# KarateLight.net
KiCad netlist of a schematic drawn in EAGLE
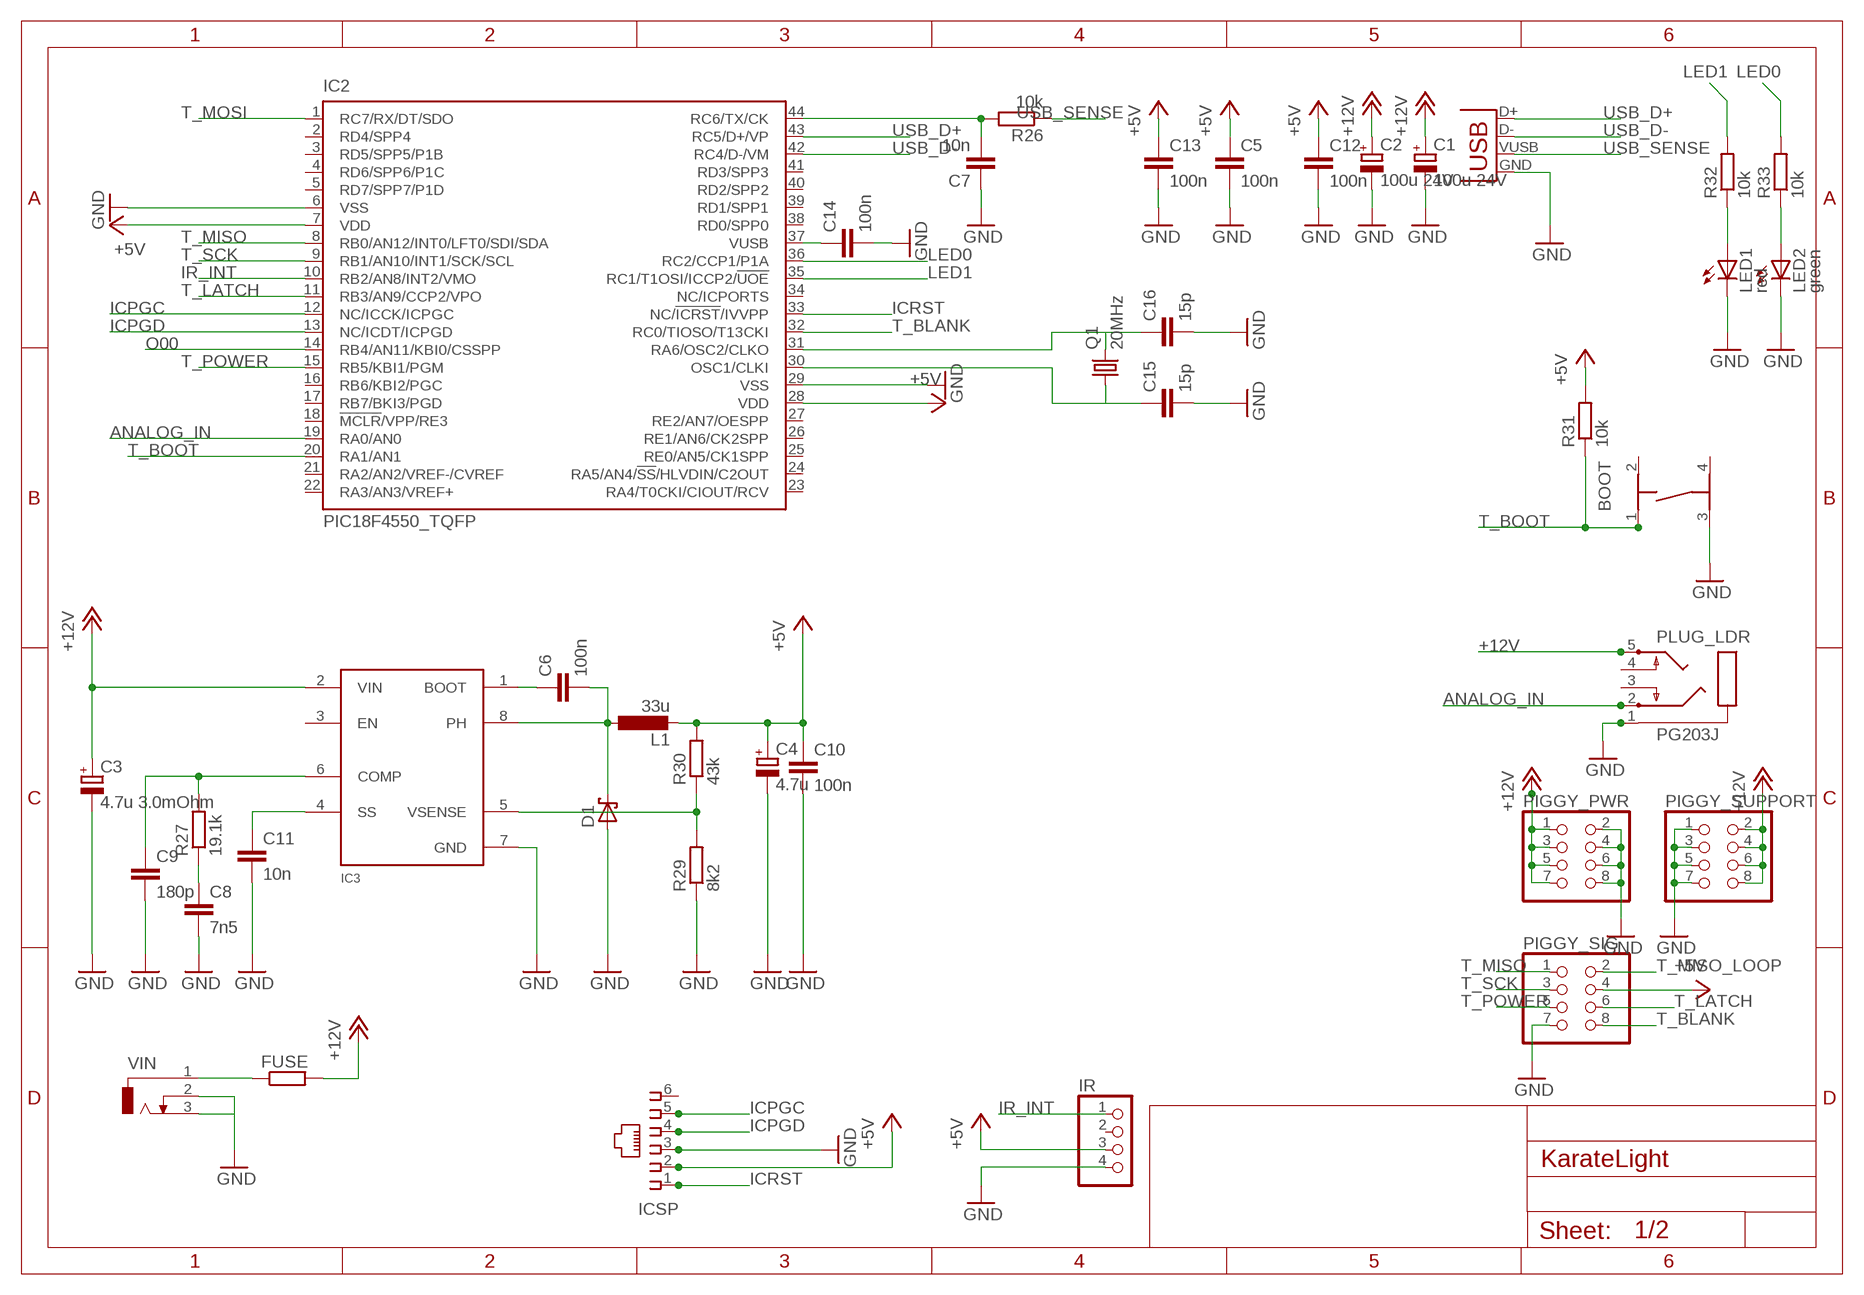
[diagram p0: schematic, sheet 1]
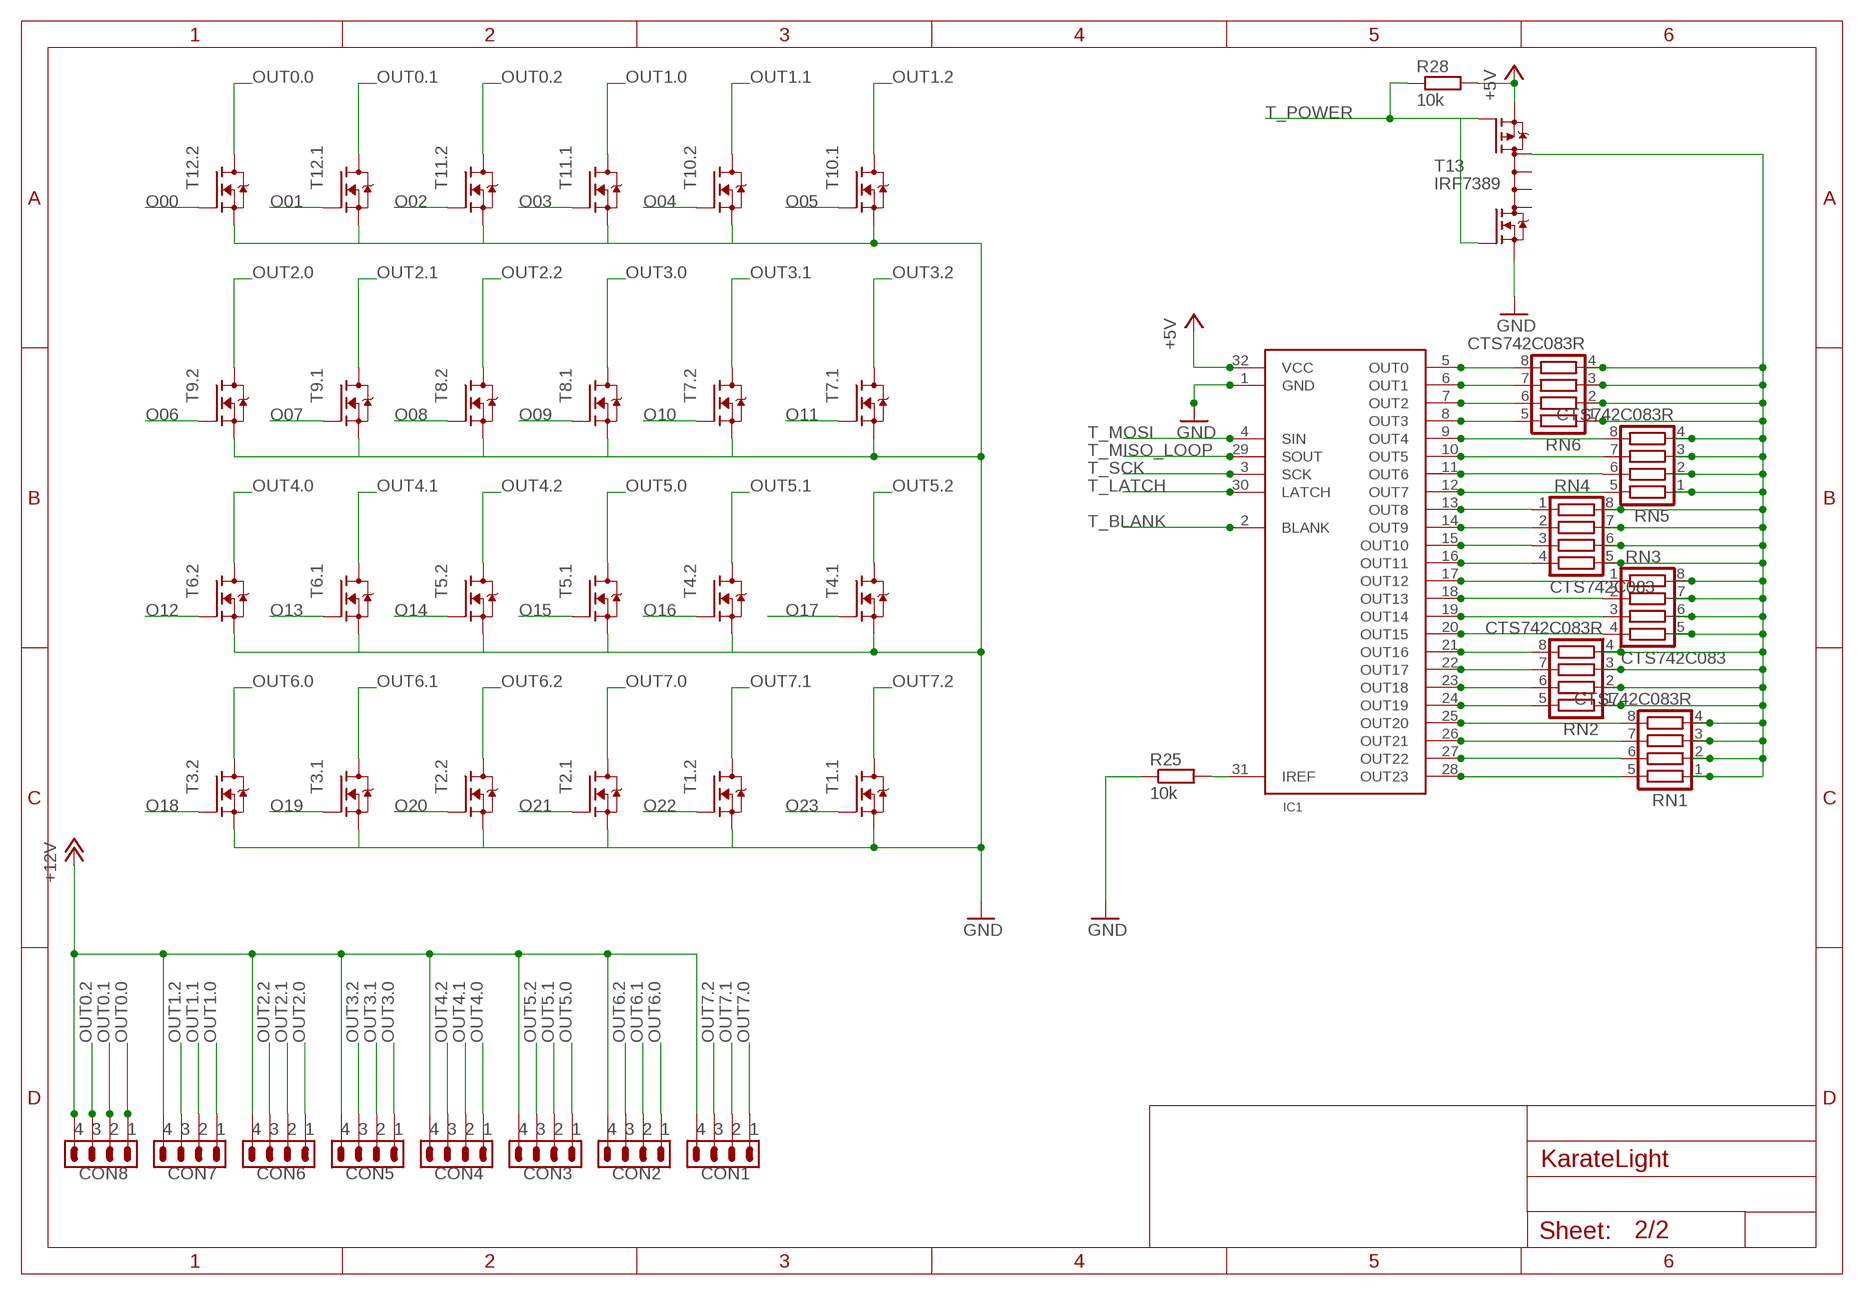
[diagram p1: schematic, sheet 2]

(export (version "E")
  (design (tool "Eeschema 10.0.6"))
  (components
    (comp (ref "CON1")
      (value "PINHEAD_4W")
      (footprint "eagle-import:MA04-1")
      (libsource (lib "eagle-import") (part "PINHEAD_4W"))
    )
    (comp (ref "CON2")
      (value "PINHEAD_4W")
      (footprint "eagle-import:MA04-1")
      (libsource (lib "eagle-import") (part "PINHEAD_4W"))
    )
    (comp (ref "CON3")
      (value "PINHEAD_4W")
      (footprint "eagle-import:MA04-1")
      (libsource (lib "eagle-import") (part "PINHEAD_4W"))
    )
    (comp (ref "CON4")
      (value "PINHEAD_4W")
      (footprint "eagle-import:MA04-1")
      (libsource (lib "eagle-import") (part "PINHEAD_4W"))
    )
    (comp (ref "CON5")
      (value "PINHEAD_4W")
      (footprint "eagle-import:MA04-1")
      (libsource (lib "eagle-import") (part "PINHEAD_4W"))
    )
    (comp (ref "CON6")
      (value "PINHEAD_4W")
      (footprint "eagle-import:MA04-1")
      (libsource (lib "eagle-import") (part "PINHEAD_4W"))
    )
    (comp (ref "CON7")
      (value "PINHEAD_4W")
      (footprint "eagle-import:MA04-1")
      (libsource (lib "eagle-import") (part "PINHEAD_4W"))
    )
    (comp (ref "CON8")
      (value "PINHEAD_4W")
      (footprint "eagle-import:MA04-1")
      (libsource (lib "eagle-import") (part "PINHEAD_4W"))
    )
    (comp (ref "IC1")
      (value "TLC5947")
      (footprint "eagle-import:TSSOP32")
      (libsource (lib "eagle-import") (part "TLC5947"))
    )
    (comp (ref "R25")
      (value "10k")
      (footprint "eagle-import:R0603")
      (libsource (lib "eagle-import") (part "R-EU_R0603"))
    )
    (comp (ref "R28")
      (value "10k")
      (footprint "eagle-import:R0603")
      (libsource (lib "eagle-import") (part "R-EU_R0603"))
    )
    (comp (ref "RN1")
      (value "CTS742C083R")
      (footprint "eagle-import:CTS742C083")
      (libsource (lib "eagle-import") (part "CTS742C083R"))
    )
    (comp (ref "RN2")
      (value "CTS742C083R")
      (footprint "eagle-import:CTS742C083")
      (libsource (lib "eagle-import") (part "CTS742C083R"))
    )
    (comp (ref "RN3")
      (value "CTS742C083")
      (footprint "eagle-import:CTS742C083")
      (fields (field (name "OC_FARNELL") "unknown") (field (name "OC_NEWARK") "unknown"))
      (libsource (lib "eagle-import") (part "CTS742C083"))
    )
    (comp (ref "RN4")
      (value "CTS742C083")
      (footprint "eagle-import:CTS742C083")
      (libsource (lib "eagle-import") (part "CTS742C083"))
    )
    (comp (ref "RN5")
      (value "CTS742C083R")
      (footprint "eagle-import:CTS742C083")
      (libsource (lib "eagle-import") (part "CTS742C083R"))
    )
    (comp (ref "RN6")
      (value "CTS742C083R")
      (footprint "eagle-import:CTS742C083")
      (libsource (lib "eagle-import") (part "CTS742C083R"))
    )
    (comp (ref "T1")
      (value "IRF7103")
      (footprint "eagle-import:SO08-IRF")
      (libsource (lib "eagle-import") (part "IRF7103"))
    )
    (comp (ref "T2")
      (value "IRF7103")
      (footprint "eagle-import:SO08-IRF")
      (libsource (lib "eagle-import") (part "IRF7103"))
    )
    (comp (ref "T3")
      (value "IRF7103")
      (footprint "eagle-import:SO08-IRF")
      (libsource (lib "eagle-import") (part "IRF7103"))
    )
    (comp (ref "T4")
      (value "IRF7103")
      (footprint "eagle-import:SO08-IRF")
      (libsource (lib "eagle-import") (part "IRF7103"))
    )
    (comp (ref "T5")
      (value "IRF7103")
      (footprint "eagle-import:SO08-IRF")
      (libsource (lib "eagle-import") (part "IRF7103"))
    )
    (comp (ref "T6")
      (value "IRF7103")
      (footprint "eagle-import:SO08-IRF")
      (libsource (lib "eagle-import") (part "IRF7103"))
    )
    (comp (ref "T7")
      (value "IRF7103")
      (footprint "eagle-import:SO08-IRF")
      (libsource (lib "eagle-import") (part "IRF7103"))
    )
    (comp (ref "T8")
      (value "IRF7103")
      (footprint "eagle-import:SO08-IRF")
      (libsource (lib "eagle-import") (part "IRF7103"))
    )
    (comp (ref "T9")
      (value "IRF7103")
      (footprint "eagle-import:SO08-IRF")
      (libsource (lib "eagle-import") (part "IRF7103"))
    )
    (comp (ref "T10")
      (value "IRF7103")
      (footprint "eagle-import:SO08-IRF")
      (libsource (lib "eagle-import") (part "IRF7103"))
    )
    (comp (ref "T11")
      (value "IRF7103")
      (footprint "eagle-import:SO08-IRF")
      (libsource (lib "eagle-import") (part "IRF7103"))
    )
    (comp (ref "T12")
      (value "IRF7103")
      (footprint "eagle-import:SO08-IRF")
      (libsource (lib "eagle-import") (part "IRF7103"))
    )
    (comp (ref "T13")
      (value "IRF7389")
      (footprint "eagle-import:SO08-IRF")
      (libsource (lib "eagle-import") (part "IRF7389"))
    )
    (comp (ref "BOOT")
      (value "TASTER-9314_SMD")
      (footprint "eagle-import:TASTER-9314_SMD")
      (libsource (lib "eagle-import") (part "TASTER-9314_SMD"))
    )
    (comp (ref "C1")
      (value "100u 24V")
      (footprint "eagle-import:153CLV-0605")
      (libsource (lib "eagle-import") (part "CPOL-EU153CLV-0605"))
    )
    (comp (ref "C2")
      (value "100u 24V")
      (footprint "eagle-import:153CLV-0605")
      (libsource (lib "eagle-import") (part "CPOL-EU153CLV-0605"))
    )
    (comp (ref "C3")
      (value "4.7u 3.0mOhm")
      (footprint "eagle-import:153CLV-0405")
      (libsource (lib "eagle-import") (part "CPOL-EU153CLV-0405"))
    )
    (comp (ref "C4")
      (value "4.7u")
      (footprint "eagle-import:153CLV-0405")
      (libsource (lib "eagle-import") (part "CPOL-EU153CLV-0405"))
    )
    (comp (ref "C5")
      (value "100n")
      (footprint "eagle-import:C0805K")
      (libsource (lib "eagle-import") (part "C-EUC0805K"))
    )
    (comp (ref "C6")
      (value "100n")
      (footprint "eagle-import:C0603")
      (libsource (lib "eagle-import") (part "C-EUC0603"))
    )
    (comp (ref "C7")
      (value "10n")
      (footprint "eagle-import:C0603")
      (libsource (lib "eagle-import") (part "C-EUC0603"))
    )
    (comp (ref "C8")
      (value "7n5")
      (footprint "eagle-import:C0603")
      (libsource (lib "eagle-import") (part "C-EUC0603"))
    )
    (comp (ref "C9")
      (value "180p")
      (footprint "eagle-import:C0603")
      (libsource (lib "eagle-import") (part "C-EUC0603"))
    )
    (comp (ref "C10")
      (value "100n")
      (footprint "eagle-import:C0603")
      (libsource (lib "eagle-import") (part "C-EUC0603"))
    )
    (comp (ref "C11")
      (value "10n")
      (footprint "eagle-import:C0603")
      (libsource (lib "eagle-import") (part "C-EUC0603"))
    )
    (comp (ref "C12")
      (value "100n")
      (footprint "eagle-import:C0603")
      (libsource (lib "eagle-import") (part "C-EUC0603"))
    )
    (comp (ref "C13")
      (value "100n")
      (footprint "eagle-import:C0805K")
      (libsource (lib "eagle-import") (part "C-EUC0805K"))
    )
    (comp (ref "C14")
      (value "100n")
      (footprint "eagle-import:C0805K")
      (libsource (lib "eagle-import") (part "C-EUC0805K"))
    )
    (comp (ref "C15")
      (value "15p")
      (footprint "eagle-import:C0603")
      (libsource (lib "eagle-import") (part "C-EUC0603"))
    )
    (comp (ref "C16")
      (value "15p")
      (footprint "eagle-import:C0603")
      (libsource (lib "eagle-import") (part "C-EUC0603"))
    )
    (comp (ref "D1")
      (value "SCHOTTKY-DIODESMD")
      (footprint "eagle-import:SMB")
      (libsource (lib "eagle-import") (part "SCHOTTKY-DIODESMD"))
    )
    (comp (ref "FUSE")
      (value "R-EU_R4527")
      (footprint "eagle-import:R4527")
      (libsource (lib "eagle-import") (part "R-EU_R4527"))
    )
    (comp (ref "IC2")
      (value "PIC18F4550_TQFP")
      (footprint "eagle-import:TQFP44")
      (libsource (lib "eagle-import") (part "PIC18F4_TQFP550"))
    )
    (comp (ref "IC3")
      (value "TPS54232")
      (footprint "eagle-import:SO-08")
      (libsource (lib "eagle-import") (part "TPS54232"))
    )
    (comp (ref "ICSP")
      (value "520250-3")
      (footprint "eagle-import:520250-3")
      (libsource (lib "eagle-import") (part "520250-3"))
    )
    (comp (ref "IR")
      (value "PINHD-1X4")
      (footprint "eagle-import:1X04")
      (libsource (lib "eagle-import") (part "PINHD-1X4"))
    )
    (comp (ref "L1")
      (value "33u")
      (footprint "eagle-import:PIS2816")
      (libsource (lib "eagle-import") (part "L-EUPIS2816"))
    )
    (comp (ref "LED1")
      (value "red")
      (footprint "eagle-import:CHIP-LED0805")
      (libsource (lib "eagle-import") (part "LEDCHIP-LED0805"))
    )
    (comp (ref "LED2")
      (value "green")
      (footprint "eagle-import:CHIP-LED0805")
      (libsource (lib "eagle-import") (part "LEDCHIP-LED0805"))
    )
    (comp (ref "PIGGY_PWR")
      (value "PINHD-2X4")
      (footprint "eagle-import:2X04")
      (libsource (lib "eagle-import") (part "PINHD-2X4"))
    )
    (comp (ref "PIGGY_SIG")
      (value "PINHD-2X4")
      (footprint "eagle-import:2X04")
      (libsource (lib "eagle-import") (part "PINHD-2X4"))
    )
    (comp (ref "PIGGY_SUPPORT")
      (value "PINHD-2X4")
      (footprint "eagle-import:2X04")
      (libsource (lib "eagle-import") (part "PINHD-2X4"))
    )
    (comp (ref "PLUG_LDR")
      (value "PG203J")
      (footprint "eagle-import:PG203J")
      (libsource (lib "eagle-import") (part "PG203J"))
    )
    (comp (ref "PLUG_USB")
      (value "USB-B-S")
      (footprint "eagle-import:USB-B-SMT")
      (libsource (lib "eagle-import") (part "USB-B-S"))
    )
    (comp (ref "Q1")
      (value "20MHz")
      (footprint "eagle-import:HC49UP")
      (libsource (lib "eagle-import") (part "CRYSTALHC49UP"))
    )
    (comp (ref "R26")
      (value "10k")
      (footprint "eagle-import:R0603")
      (libsource (lib "eagle-import") (part "R-EU_R0603"))
    )
    (comp (ref "R27")
      (value "19.1k")
      (footprint "eagle-import:R0603")
      (libsource (lib "eagle-import") (part "R-EU_R0603"))
    )
    (comp (ref "R29")
      (value "8k2")
      (footprint "eagle-import:R0603")
      (libsource (lib "eagle-import") (part "R-EU_R0603"))
    )
    (comp (ref "R30")
      (value "43k")
      (footprint "eagle-import:R0603")
      (libsource (lib "eagle-import") (part "R-EU_R0603"))
    )
    (comp (ref "R31")
      (value "10k")
      (footprint "eagle-import:R0603")
      (libsource (lib "eagle-import") (part "R-EU_R0603"))
    )
    (comp (ref "R32")
      (value "10k")
      (footprint "eagle-import:R0603")
      (libsource (lib "eagle-import") (part "R-EU_R0603"))
    )
    (comp (ref "R33")
      (value "10k")
      (footprint "eagle-import:R0603")
      (libsource (lib "eagle-import") (part "R-EU_R0603"))
    )
    (comp (ref "VIN")
      (value "DCJ0303")
      (footprint "eagle-import:DCJ0303")
      (libsource (lib "eagle-import") (part "DCJ0303"))
    )
  )
  (nets
    (net (code "1") (name "+5V") (class "Default")
      (node (ref "C10") (pin "1") (pinfunction "1_1") (pintype "passive"))
      (node (ref "C12") (pin "1") (pinfunction "1_1") (pintype "passive"))
      (node (ref "C13") (pin "1") (pinfunction "1_1") (pintype "passive"))
      (node (ref "C4") (pin "+") (pinfunction "+_+") (pintype "passive"))
      (node (ref "C5") (pin "1") (pinfunction "1_1") (pintype "passive"))
      (node (ref "IC1") (pin "32") (pinfunction "VCC_32") (pintype "bidirectional"))
      (node (ref "IC2") (pin "28") (pinfunction "VDD_28") (pintype "power_in"))
      (node (ref "IC2") (pin "7") (pinfunction "VDD_7") (pintype "power_in"))
      (node (ref "ICSP") (pin "2") (pinfunction "2_2") (pintype "passive"))
      (node (ref "IR") (pin "3") (pinfunction "3_3") (pintype "passive"))
      (node (ref "L1") (pin "2") (pinfunction "2_2") (pintype "passive"))
      (node (ref "PIGGY_SIG") (pin "4") (pinfunction "4_4") (pintype "passive"))
      (node (ref "R28") (pin "2") (pinfunction "2_2") (pintype "passive"))
      (node (ref "R30") (pin "2") (pinfunction "2_2") (pintype "passive"))
      (node (ref "R31") (pin "2") (pinfunction "2_2") (pintype "passive"))
      (node (ref "T13") (pin "3") (pinfunction "P-S_3") (pintype "passive"))
    )
    (net (code "2") (name "+12V") (class "Default")
      (node (ref "C1") (pin "+") (pinfunction "+_+") (pintype "passive"))
      (node (ref "C2") (pin "+") (pinfunction "+_+") (pintype "passive"))
      (node (ref "C3") (pin "+") (pinfunction "+_+") (pintype "passive"))
      (node (ref "CON1") (pin "4") (pinfunction "4_4") (pintype "bidirectional"))
      (node (ref "CON2") (pin "4") (pinfunction "4_4") (pintype "bidirectional"))
      (node (ref "CON3") (pin "4") (pinfunction "4_4") (pintype "bidirectional"))
      (node (ref "CON4") (pin "4") (pinfunction "4_4") (pintype "bidirectional"))
      (node (ref "CON5") (pin "4") (pinfunction "4_4") (pintype "bidirectional"))
      (node (ref "CON6") (pin "4") (pinfunction "4_4") (pintype "bidirectional"))
      (node (ref "CON7") (pin "4") (pinfunction "4_4") (pintype "bidirectional"))
      (node (ref "CON8") (pin "4") (pinfunction "4_4") (pintype "bidirectional"))
      (node (ref "FUSE") (pin "2") (pinfunction "2_2") (pintype "passive"))
      (node (ref "IC3") (pin "2") (pinfunction "VIN_2") (pintype "bidirectional"))
      (node (ref "PIGGY_PWR") (pin "1") (pinfunction "1_1") (pintype "passive"))
      (node (ref "PIGGY_PWR") (pin "3") (pinfunction "3_3") (pintype "passive"))
      (node (ref "PIGGY_PWR") (pin "5") (pinfunction "5_5") (pintype "passive"))
      (node (ref "PIGGY_PWR") (pin "7") (pinfunction "7_7") (pintype "passive"))
      (node (ref "PIGGY_SUPPORT") (pin "2") (pinfunction "2_2") (pintype "passive"))
      (node (ref "PIGGY_SUPPORT") (pin "4") (pinfunction "4_4") (pintype "passive"))
      (node (ref "PIGGY_SUPPORT") (pin "6") (pinfunction "6_6") (pintype "passive"))
      (node (ref "PIGGY_SUPPORT") (pin "8") (pinfunction "8_8") (pintype "passive"))
      (node (ref "PLUG_LDR") (pin "5") (pinfunction "5_5") (pintype "passive"))
    )
    (net (code "3") (name "ANALOG_IN") (class "Default")
      (node (ref "IC2") (pin "19") (pinfunction "RA0/AN0_19") (pintype "bidirectional"))
      (node (ref "PLUG_LDR") (pin "2") (pinfunction "2_2") (pintype "passive"))
    )
    (net (code "4") (name "GND") (class "Default")
      (node (ref "BOOT") (pin "3") (pinfunction "3_3") (pintype "passive"))
      (node (ref "C1") (pin "-") (pinfunction "-_-") (pintype "passive"))
      (node (ref "C10") (pin "2") (pinfunction "2_2") (pintype "passive"))
      (node (ref "C11") (pin "2") (pinfunction "2_2") (pintype "passive"))
      (node (ref "C12") (pin "2") (pinfunction "2_2") (pintype "passive"))
      (node (ref "C13") (pin "2") (pinfunction "2_2") (pintype "passive"))
      (node (ref "C14") (pin "2") (pinfunction "2_2") (pintype "passive"))
      (node (ref "C15") (pin "2") (pinfunction "2_2") (pintype "passive"))
      (node (ref "C16") (pin "2") (pinfunction "2_2") (pintype "passive"))
      (node (ref "C2") (pin "-") (pinfunction "-_-") (pintype "passive"))
      (node (ref "C3") (pin "-") (pinfunction "-_-") (pintype "passive"))
      (node (ref "C4") (pin "-") (pinfunction "-_-") (pintype "passive"))
      (node (ref "C5") (pin "2") (pinfunction "2_2") (pintype "passive"))
      (node (ref "C7") (pin "1") (pinfunction "1_1") (pintype "passive"))
      (node (ref "C8") (pin "2") (pinfunction "2_2") (pintype "passive"))
      (node (ref "C9") (pin "2") (pinfunction "2_2") (pintype "passive"))
      (node (ref "D1") (pin "A") (pinfunction "A_A") (pintype "passive"))
      (node (ref "IC1") (pin "1") (pinfunction "GND_1") (pintype "bidirectional"))
      (node (ref "IC2") (pin "29") (pinfunction "VSS_29") (pintype "power_in"))
      (node (ref "IC2") (pin "6") (pinfunction "VSS_6") (pintype "power_in"))
      (node (ref "IC3") (pin "7") (pinfunction "GND_7") (pintype "bidirectional"))
      (node (ref "ICSP") (pin "3") (pinfunction "3_3") (pintype "passive"))
      (node (ref "IR") (pin "4") (pinfunction "4_4") (pintype "passive"))
      (node (ref "LED1") (pin "C") (pinfunction "C_C") (pintype "passive"))
      (node (ref "LED2") (pin "C") (pinfunction "C_C") (pintype "passive"))
      (node (ref "PIGGY_PWR") (pin "2") (pinfunction "2_2") (pintype "passive"))
      (node (ref "PIGGY_PWR") (pin "4") (pinfunction "4_4") (pintype "passive"))
      (node (ref "PIGGY_PWR") (pin "6") (pinfunction "6_6") (pintype "passive"))
      (node (ref "PIGGY_PWR") (pin "8") (pinfunction "8_8") (pintype "passive"))
      (node (ref "PIGGY_SIG") (pin "7") (pinfunction "7_7") (pintype "passive"))
      (node (ref "PIGGY_SUPPORT") (pin "1") (pinfunction "1_1") (pintype "passive"))
      (node (ref "PIGGY_SUPPORT") (pin "3") (pinfunction "3_3") (pintype "passive"))
      (node (ref "PIGGY_SUPPORT") (pin "5") (pinfunction "5_5") (pintype "passive"))
      (node (ref "PIGGY_SUPPORT") (pin "7") (pinfunction "7_7") (pintype "passive"))
      (node (ref "PLUG_LDR") (pin "1") (pinfunction "1_1") (pintype "passive"))
      (node (ref "PLUG_USB") (pin "GND") (pinfunction "GND_GND") (pintype "bidirectional"))
      (node (ref "R25") (pin "1") (pinfunction "1_1") (pintype "passive"))
      (node (ref "R29") (pin "1") (pinfunction "1_1") (pintype "passive"))
      (node (ref "T1") (pin "1") (pinfunction "S_1") (pintype "passive"))
      (node (ref "T1") (pin "3") (pinfunction "S_3") (pintype "passive"))
      (node (ref "T10") (pin "1") (pinfunction "S_1") (pintype "passive"))
      (node (ref "T10") (pin "3") (pinfunction "S_3") (pintype "passive"))
      (node (ref "T11") (pin "1") (pinfunction "S_1") (pintype "passive"))
      (node (ref "T11") (pin "3") (pinfunction "S_3") (pintype "passive"))
      (node (ref "T12") (pin "1") (pinfunction "S_1") (pintype "passive"))
      (node (ref "T12") (pin "3") (pinfunction "S_3") (pintype "passive"))
      (node (ref "T13") (pin "1") (pinfunction "N-S_1") (pintype "passive"))
      (node (ref "T2") (pin "1") (pinfunction "S_1") (pintype "passive"))
      (node (ref "T2") (pin "3") (pinfunction "S_3") (pintype "passive"))
      (node (ref "T3") (pin "1") (pinfunction "S_1") (pintype "passive"))
      (node (ref "T3") (pin "3") (pinfunction "S_3") (pintype "passive"))
      (node (ref "T4") (pin "1") (pinfunction "S_1") (pintype "passive"))
      (node (ref "T4") (pin "3") (pinfunction "S_3") (pintype "passive"))
      (node (ref "T5") (pin "1") (pinfunction "S_1") (pintype "passive"))
      (node (ref "T5") (pin "3") (pinfunction "S_3") (pintype "passive"))
      (node (ref "T6") (pin "1") (pinfunction "S_1") (pintype "passive"))
      (node (ref "T6") (pin "3") (pinfunction "S_3") (pintype "passive"))
      (node (ref "T7") (pin "1") (pinfunction "S_1") (pintype "passive"))
      (node (ref "T7") (pin "3") (pinfunction "S_3") (pintype "passive"))
      (node (ref "T8") (pin "1") (pinfunction "S_1") (pintype "passive"))
      (node (ref "T8") (pin "3") (pinfunction "S_3") (pintype "passive"))
      (node (ref "T9") (pin "1") (pinfunction "S_1") (pintype "passive"))
      (node (ref "T9") (pin "3") (pinfunction "S_3") (pintype "passive"))
      (node (ref "VIN") (pin "2") (pinfunction "2_2") (pintype "passive"))
      (node (ref "VIN") (pin "3") (pinfunction "3_3") (pintype "passive"))
    )
    (net (code "5") (name "ICPGC") (class "Default")
      (node (ref "IC2") (pin "12") (pinfunction "NC/ICCK/ICPGC_12") (pintype "bidirectional"))
      (node (ref "ICSP") (pin "5") (pinfunction "5_5") (pintype "passive"))
    )
    (net (code "6") (name "ICPGD") (class "Default")
      (node (ref "IC2") (pin "13") (pinfunction "NC/ICDT/ICPGD_13") (pintype "bidirectional"))
      (node (ref "ICSP") (pin "4") (pinfunction "4_4") (pintype "passive"))
    )
    (net (code "7") (name "ICRST") (class "Default")
      (node (ref "IC2") (pin "33") (pinfunction "NC/~{ICRST}/IVVPP_33") (pintype "input"))
      (node (ref "ICSP") (pin "1") (pinfunction "1_1") (pintype "passive"))
    )
    (net (code "8") (name "IR_INT") (class "Default")
      (node (ref "IC2") (pin "10") (pinfunction "RB2/AN8/INT2/VMO_10") (pintype "bidirectional"))
      (node (ref "IR") (pin "1") (pinfunction "1_1") (pintype "passive"))
    )
    (net (code "9") (name "LED0") (class "Default")
      (node (ref "IC2") (pin "36") (pinfunction "RC2/CCP1/P1A_36") (pintype "bidirectional"))
      (node (ref "R33") (pin "2") (pinfunction "2_2") (pintype "passive"))
    )
    (net (code "10") (name "LED1") (class "Default")
      (node (ref "IC2") (pin "35") (pinfunction "RC1/T1OSI/ICCP2/~{UOE}_35") (pintype "bidirectional"))
      (node (ref "R32") (pin "2") (pinfunction "2_2") (pintype "passive"))
    )
    (net (code "11") (name "Net-(C8-Pad1)") (class "Default")
      (node (ref "C8") (pin "1") (pinfunction "1_1") (pintype "passive"))
      (node (ref "R27") (pin "1") (pinfunction "1_1") (pintype "passive"))
    )
    (net (code "12") (name "Net-(FUSE-Pad1)") (class "Default")
      (node (ref "FUSE") (pin "1") (pinfunction "1_1") (pintype "passive"))
      (node (ref "VIN") (pin "1") (pinfunction "1_1") (pintype "passive"))
    )
    (net (code "13") (name "Net-(IC1-IREF)") (class "Default")
      (node (ref "IC1") (pin "31") (pinfunction "IREF_31") (pintype "bidirectional"))
      (node (ref "R25") (pin "2") (pinfunction "2_2") (pintype "passive"))
    )
    (net (code "14") (name "Net-(IC2-OSC1{slash}CLKI)") (class "Default")
      (node (ref "C15") (pin "1") (pinfunction "1_1") (pintype "passive"))
      (node (ref "IC2") (pin "30") (pinfunction "OSC1/CLKI_30") (pintype "input"))
      (node (ref "Q1") (pin "1") (pinfunction "1_1") (pintype "passive"))
    )
    (net (code "15") (name "Net-(IC2-RA6{slash}OSC2{slash}CLKO)") (class "Default")
      (node (ref "C16") (pin "1") (pinfunction "1_1") (pintype "passive"))
      (node (ref "IC2") (pin "31") (pinfunction "RA6/OSC2/CLKO_31") (pintype "output"))
      (node (ref "Q1") (pin "2") (pinfunction "2_2") (pintype "passive"))
    )
    (net (code "16") (name "Net-(IC2-RC6{slash}TX{slash}CK)") (class "Default")
      (node (ref "C7") (pin "2") (pinfunction "2_2") (pintype "passive"))
      (node (ref "IC2") (pin "44") (pinfunction "RC6/TX/CK_44") (pintype "bidirectional"))
      (node (ref "R26") (pin "2") (pinfunction "2_2") (pintype "passive"))
    )
    (net (code "17") (name "Net-(IC2-VUSB)") (class "Default")
      (node (ref "C14") (pin "1") (pinfunction "1_1") (pintype "passive"))
      (node (ref "IC2") (pin "37") (pinfunction "VUSB_37") (pintype "bidirectional"))
    )
    (net (code "18") (name "Net-(IC3-BOOT)") (class "Default")
      (node (ref "C6") (pin "1") (pinfunction "1_1") (pintype "passive"))
      (node (ref "IC3") (pin "1") (pinfunction "BOOT_1") (pintype "bidirectional"))
    )
    (net (code "19") (name "Net-(IC3-COMP)") (class "Default")
      (node (ref "C9") (pin "1") (pinfunction "1_1") (pintype "passive"))
      (node (ref "IC3") (pin "6") (pinfunction "COMP_6") (pintype "bidirectional"))
      (node (ref "R27") (pin "2") (pinfunction "2_2") (pintype "passive"))
    )
    (net (code "20") (name "Net-(IC3-PH)") (class "Default")
      (node (ref "C6") (pin "2") (pinfunction "2_2") (pintype "passive"))
      (node (ref "D1") (pin "C") (pinfunction "C_C") (pintype "passive"))
      (node (ref "IC3") (pin "8") (pinfunction "PH_8") (pintype "bidirectional"))
      (node (ref "L1") (pin "1") (pinfunction "1_1") (pintype "passive"))
    )
    (net (code "21") (name "Net-(IC3-SS)") (class "Default")
      (node (ref "C11") (pin "1") (pinfunction "1_1") (pintype "passive"))
      (node (ref "IC3") (pin "4") (pinfunction "SS_4") (pintype "bidirectional"))
    )
    (net (code "22") (name "Net-(IC3-VSENSE)") (class "Default")
      (node (ref "IC3") (pin "5") (pinfunction "VSENSE_5") (pintype "bidirectional"))
      (node (ref "R29") (pin "2") (pinfunction "2_2") (pintype "passive"))
      (node (ref "R30") (pin "1") (pinfunction "1_1") (pintype "passive"))
    )
    (net (code "23") (name "Net-(LED1-PadA)") (class "Default")
      (node (ref "LED1") (pin "A") (pinfunction "A_A") (pintype "passive"))
      (node (ref "R32") (pin "1") (pinfunction "1_1") (pintype "passive"))
    )
    (net (code "24") (name "Net-(LED2-PadA)") (class "Default")
      (node (ref "LED2") (pin "A") (pinfunction "A_A") (pintype "passive"))
      (node (ref "R33") (pin "1") (pinfunction "1_1") (pintype "passive"))
    )
    (net (code "25") (name "Net-(RN1-Pad1)") (class "Default")
      (node (ref "RN1") (pin "1") (pinfunction "1_1") (pintype "passive"))
      (node (ref "RN1") (pin "2") (pinfunction "2_2") (pintype "passive"))
      (node (ref "RN1") (pin "3") (pinfunction "3_3") (pintype "passive"))
      (node (ref "RN1") (pin "4") (pinfunction "4_4") (pintype "passive"))
      (node (ref "RN2") (pin "1") (pinfunction "1_1") (pintype "passive"))
      (node (ref "RN2") (pin "2") (pinfunction "2_2") (pintype "passive"))
      (node (ref "RN2") (pin "3") (pinfunction "3_3") (pintype "passive"))
      (node (ref "RN2") (pin "4") (pinfunction "4_4") (pintype "passive"))
      (node (ref "RN3") (pin "5") (pinfunction "5_5") (pintype "passive"))
      (node (ref "RN3") (pin "6") (pinfunction "6_6") (pintype "passive"))
      (node (ref "RN3") (pin "7") (pinfunction "7_7") (pintype "passive"))
      (node (ref "RN3") (pin "8") (pinfunction "8_8") (pintype "passive"))
      (node (ref "RN4") (pin "5") (pinfunction "5_5") (pintype "passive"))
      (node (ref "RN4") (pin "6") (pinfunction "6_6") (pintype "passive"))
      (node (ref "RN4") (pin "7") (pinfunction "7_7") (pintype "passive"))
      (node (ref "RN4") (pin "8") (pinfunction "8_8") (pintype "passive"))
      (node (ref "RN5") (pin "1") (pinfunction "1_1") (pintype "passive"))
      (node (ref "RN5") (pin "2") (pinfunction "2_2") (pintype "passive"))
      (node (ref "RN5") (pin "3") (pinfunction "3_3") (pintype "passive"))
      (node (ref "RN5") (pin "4") (pinfunction "4_4") (pintype "passive"))
      (node (ref "RN6") (pin "1") (pinfunction "1_1") (pintype "passive"))
      (node (ref "RN6") (pin "2") (pinfunction "2_2") (pintype "passive"))
      (node (ref "RN6") (pin "3") (pinfunction "3_3") (pintype "passive"))
      (node (ref "RN6") (pin "4") (pinfunction "4_4") (pintype "passive"))
      (node (ref "T13") (pin "5") (pinfunction "D_5") (pintype "passive"))
    )
    (net (code "26") (name "O00") (class "Default")
      (node (ref "IC1") (pin "5") (pinfunction "OUT0_5") (pintype "bidirectional"))
      (node (ref "IC2") (pin "14") (pinfunction "RB4/AN11/KBI0/CSSPP_14") (pintype "bidirectional"))
      (node (ref "RN6") (pin "8") (pinfunction "5_8") (pintype "passive"))
      (node (ref "T12") (pin "4") (pinfunction "G_4") (pintype "passive"))
    )
    (net (code "27") (name "O01") (class "Default")
      (node (ref "IC1") (pin "6") (pinfunction "OUT1_6") (pintype "bidirectional"))
      (node (ref "RN6") (pin "7") (pinfunction "6_7") (pintype "passive"))
      (node (ref "T12") (pin "2") (pinfunction "G_2") (pintype "passive"))
    )
    (net (code "28") (name "O02") (class "Default")
      (node (ref "IC1") (pin "7") (pinfunction "OUT2_7") (pintype "bidirectional"))
      (node (ref "RN6") (pin "6") (pinfunction "7_6") (pintype "passive"))
      (node (ref "T11") (pin "4") (pinfunction "G_4") (pintype "passive"))
    )
    (net (code "29") (name "O03") (class "Default")
      (node (ref "IC1") (pin "8") (pinfunction "OUT3_8") (pintype "bidirectional"))
      (node (ref "RN6") (pin "5") (pinfunction "8_5") (pintype "passive"))
      (node (ref "T11") (pin "2") (pinfunction "G_2") (pintype "passive"))
    )
    (net (code "30") (name "O04") (class "Default")
      (node (ref "IC1") (pin "9") (pinfunction "OUT4_9") (pintype "bidirectional"))
      (node (ref "RN5") (pin "8") (pinfunction "5_8") (pintype "passive"))
      (node (ref "T10") (pin "4") (pinfunction "G_4") (pintype "passive"))
    )
    (net (code "31") (name "O05") (class "Default")
      (node (ref "IC1") (pin "10") (pinfunction "OUT5_10") (pintype "bidirectional"))
      (node (ref "RN5") (pin "7") (pinfunction "6_7") (pintype "passive"))
      (node (ref "T10") (pin "2") (pinfunction "G_2") (pintype "passive"))
    )
    (net (code "32") (name "O06") (class "Default")
      (node (ref "IC1") (pin "11") (pinfunction "OUT6_11") (pintype "bidirectional"))
      (node (ref "RN5") (pin "6") (pinfunction "7_6") (pintype "passive"))
      (node (ref "T9") (pin "4") (pinfunction "G_4") (pintype "passive"))
    )
    (net (code "33") (name "O07") (class "Default")
      (node (ref "IC1") (pin "12") (pinfunction "OUT7_12") (pintype "bidirectional"))
      (node (ref "RN5") (pin "5") (pinfunction "8_5") (pintype "passive"))
      (node (ref "T9") (pin "2") (pinfunction "G_2") (pintype "passive"))
    )
    (net (code "34") (name "O08") (class "Default")
      (node (ref "IC1") (pin "13") (pinfunction "OUT8_13") (pintype "bidirectional"))
      (node (ref "RN4") (pin "1") (pinfunction "1_1") (pintype "passive"))
      (node (ref "T8") (pin "4") (pinfunction "G_4") (pintype "passive"))
    )
    (net (code "35") (name "O09") (class "Default")
      (node (ref "IC1") (pin "14") (pinfunction "OUT9_14") (pintype "bidirectional"))
      (node (ref "RN4") (pin "2") (pinfunction "2_2") (pintype "passive"))
      (node (ref "T8") (pin "2") (pinfunction "G_2") (pintype "passive"))
    )
    (net (code "36") (name "O10") (class "Default")
      (node (ref "IC1") (pin "15") (pinfunction "OUT10_15") (pintype "bidirectional"))
      (node (ref "RN4") (pin "3") (pinfunction "3_3") (pintype "passive"))
      (node (ref "T7") (pin "4") (pinfunction "G_4") (pintype "passive"))
    )
    (net (code "37") (name "O11") (class "Default")
      (node (ref "IC1") (pin "16") (pinfunction "OUT11_16") (pintype "bidirectional"))
      (node (ref "RN4") (pin "4") (pinfunction "4_4") (pintype "passive"))
      (node (ref "T7") (pin "2") (pinfunction "G_2") (pintype "passive"))
    )
    (net (code "38") (name "O12") (class "Default")
      (node (ref "IC1") (pin "17") (pinfunction "OUT12_17") (pintype "bidirectional"))
      (node (ref "RN3") (pin "1") (pinfunction "1_1") (pintype "passive"))
      (node (ref "T6") (pin "4") (pinfunction "G_4") (pintype "passive"))
    )
    (net (code "39") (name "O13") (class "Default")
      (node (ref "IC1") (pin "18") (pinfunction "OUT13_18") (pintype "bidirectional"))
      (node (ref "RN3") (pin "2") (pinfunction "2_2") (pintype "passive"))
      (node (ref "T6") (pin "2") (pinfunction "G_2") (pintype "passive"))
    )
    (net (code "40") (name "O14") (class "Default")
      (node (ref "IC1") (pin "19") (pinfunction "OUT14_19") (pintype "bidirectional"))
      (node (ref "RN3") (pin "3") (pinfunction "3_3") (pintype "passive"))
      (node (ref "T5") (pin "4") (pinfunction "G_4") (pintype "passive"))
    )
    (net (code "41") (name "O15") (class "Default")
      (node (ref "IC1") (pin "20") (pinfunction "OUT15_20") (pintype "bidirectional"))
      (node (ref "RN3") (pin "4") (pinfunction "4_4") (pintype "passive"))
      (node (ref "T5") (pin "2") (pinfunction "G_2") (pintype "passive"))
    )
    (net (code "42") (name "O16") (class "Default")
      (node (ref "IC1") (pin "21") (pinfunction "OUT16_21") (pintype "bidirectional"))
      (node (ref "RN2") (pin "8") (pinfunction "5_8") (pintype "passive"))
      (node (ref "T4") (pin "4") (pinfunction "G_4") (pintype "passive"))
    )
    (net (code "43") (name "O17") (class "Default")
      (node (ref "IC1") (pin "22") (pinfunction "OUT17_22") (pintype "bidirectional"))
      (node (ref "RN2") (pin "7") (pinfunction "6_7") (pintype "passive"))
      (node (ref "T4") (pin "2") (pinfunction "G_2") (pintype "passive"))
    )
    (net (code "44") (name "O18") (class "Default")
      (node (ref "IC1") (pin "23") (pinfunction "OUT18_23") (pintype "bidirectional"))
      (node (ref "RN2") (pin "6") (pinfunction "7_6") (pintype "passive"))
      (node (ref "T3") (pin "4") (pinfunction "G_4") (pintype "passive"))
    )
    (net (code "45") (name "O19") (class "Default")
      (node (ref "IC1") (pin "24") (pinfunction "OUT19_24") (pintype "bidirectional"))
      (node (ref "RN2") (pin "5") (pinfunction "8_5") (pintype "passive"))
      (node (ref "T3") (pin "2") (pinfunction "G_2") (pintype "passive"))
    )
    (net (code "46") (name "O20") (class "Default")
      (node (ref "IC1") (pin "25") (pinfunction "OUT20_25") (pintype "bidirectional"))
      (node (ref "RN1") (pin "8") (pinfunction "5_8") (pintype "passive"))
      (node (ref "T2") (pin "4") (pinfunction "G_4") (pintype "passive"))
    )
    (net (code "47") (name "O21") (class "Default")
      (node (ref "IC1") (pin "26") (pinfunction "OUT21_26") (pintype "bidirectional"))
      (node (ref "RN1") (pin "7") (pinfunction "6_7") (pintype "passive"))
      (node (ref "T2") (pin "2") (pinfunction "G_2") (pintype "passive"))
    )
    (net (code "48") (name "O22") (class "Default")
      (node (ref "IC1") (pin "27") (pinfunction "OUT22_27") (pintype "bidirectional"))
      (node (ref "RN1") (pin "6") (pinfunction "7_6") (pintype "passive"))
      (node (ref "T1") (pin "4") (pinfunction "G_4") (pintype "passive"))
    )
    (net (code "49") (name "O23") (class "Default")
      (node (ref "IC1") (pin "28") (pinfunction "OUT23_28") (pintype "bidirectional"))
      (node (ref "RN1") (pin "5") (pinfunction "8_5") (pintype "passive"))
      (node (ref "T1") (pin "2") (pinfunction "G_2") (pintype "passive"))
    )
    (net (code "50") (name "OUT0.0") (class "Default")
      (node (ref "CON8") (pin "1") (pinfunction "1_1") (pintype "bidirectional"))
      (node (ref "T12") (pin "6") (pinfunction "D_6") (pintype "passive"))
    )
    (net (code "51") (name "OUT0.1") (class "Default")
      (node (ref "CON8") (pin "2") (pinfunction "2_2") (pintype "bidirectional"))
      (node (ref "T12") (pin "8") (pinfunction "D_8") (pintype "passive"))
    )
    (net (code "52") (name "OUT0.2") (class "Default")
      (node (ref "CON8") (pin "3") (pinfunction "3_3") (pintype "bidirectional"))
      (node (ref "T11") (pin "6") (pinfunction "D_6") (pintype "passive"))
    )
    (net (code "53") (name "OUT1.0") (class "Default")
      (node (ref "CON7") (pin "1") (pinfunction "1_1") (pintype "bidirectional"))
      (node (ref "T11") (pin "8") (pinfunction "D_8") (pintype "passive"))
    )
    (net (code "54") (name "OUT1.1") (class "Default")
      (node (ref "CON7") (pin "2") (pinfunction "2_2") (pintype "bidirectional"))
      (node (ref "T10") (pin "6") (pinfunction "D_6") (pintype "passive"))
    )
    (net (code "55") (name "OUT1.2") (class "Default")
      (node (ref "CON7") (pin "3") (pinfunction "3_3") (pintype "bidirectional"))
      (node (ref "T10") (pin "8") (pinfunction "D_8") (pintype "passive"))
    )
    (net (code "56") (name "OUT2.0") (class "Default")
      (node (ref "CON6") (pin "1") (pinfunction "1_1") (pintype "bidirectional"))
      (node (ref "T9") (pin "6") (pinfunction "D_6") (pintype "passive"))
    )
    (net (code "57") (name "OUT2.1") (class "Default")
      (node (ref "CON6") (pin "2") (pinfunction "2_2") (pintype "bidirectional"))
      (node (ref "T9") (pin "8") (pinfunction "D_8") (pintype "passive"))
    )
    (net (code "58") (name "OUT2.2") (class "Default")
      (node (ref "CON6") (pin "3") (pinfunction "3_3") (pintype "bidirectional"))
      (node (ref "T8") (pin "6") (pinfunction "D_6") (pintype "passive"))
    )
    (net (code "59") (name "OUT3.0") (class "Default")
      (node (ref "CON5") (pin "1") (pinfunction "1_1") (pintype "bidirectional"))
      (node (ref "T8") (pin "8") (pinfunction "D_8") (pintype "passive"))
    )
    (net (code "60") (name "OUT3.1") (class "Default")
      (node (ref "CON5") (pin "2") (pinfunction "2_2") (pintype "bidirectional"))
      (node (ref "T7") (pin "6") (pinfunction "D_6") (pintype "passive"))
    )
    (net (code "61") (name "OUT3.2") (class "Default")
      (node (ref "CON5") (pin "3") (pinfunction "3_3") (pintype "bidirectional"))
      (node (ref "T7") (pin "8") (pinfunction "D_8") (pintype "passive"))
    )
    (net (code "62") (name "OUT4.0") (class "Default")
      (node (ref "CON4") (pin "1") (pinfunction "1_1") (pintype "bidirectional"))
      (node (ref "T6") (pin "6") (pinfunction "D_6") (pintype "passive"))
    )
    (net (code "63") (name "OUT4.1") (class "Default")
      (node (ref "CON4") (pin "2") (pinfunction "2_2") (pintype "bidirectional"))
      (node (ref "T6") (pin "8") (pinfunction "D_8") (pintype "passive"))
    )
    (net (code "64") (name "OUT4.2") (class "Default")
      (node (ref "CON4") (pin "3") (pinfunction "3_3") (pintype "bidirectional"))
      (node (ref "T5") (pin "6") (pinfunction "D_6") (pintype "passive"))
    )
    (net (code "65") (name "OUT5.0") (class "Default")
      (node (ref "CON3") (pin "1") (pinfunction "1_1") (pintype "bidirectional"))
      (node (ref "T5") (pin "8") (pinfunction "D_8") (pintype "passive"))
    )
    (net (code "66") (name "OUT5.1") (class "Default")
      (node (ref "CON3") (pin "2") (pinfunction "2_2") (pintype "bidirectional"))
      (node (ref "T4") (pin "6") (pinfunction "D_6") (pintype "passive"))
    )
    (net (code "67") (name "OUT5.2") (class "Default")
      (node (ref "CON3") (pin "3") (pinfunction "3_3") (pintype "bidirectional"))
      (node (ref "T4") (pin "8") (pinfunction "D_8") (pintype "passive"))
    )
    (net (code "68") (name "OUT6.0") (class "Default")
      (node (ref "CON2") (pin "1") (pinfunction "1_1") (pintype "bidirectional"))
      (node (ref "T3") (pin "6") (pinfunction "D_6") (pintype "passive"))
    )
    (net (code "69") (name "OUT6.1") (class "Default")
      (node (ref "CON2") (pin "2") (pinfunction "2_2") (pintype "bidirectional"))
      (node (ref "T3") (pin "8") (pinfunction "D_8") (pintype "passive"))
    )
    (net (code "70") (name "OUT6.2") (class "Default")
      (node (ref "CON2") (pin "3") (pinfunction "3_3") (pintype "bidirectional"))
      (node (ref "T2") (pin "6") (pinfunction "D_6") (pintype "passive"))
    )
    (net (code "71") (name "OUT7.0") (class "Default")
      (node (ref "CON1") (pin "1") (pinfunction "1_1") (pintype "bidirectional"))
      (node (ref "T2") (pin "8") (pinfunction "D_8") (pintype "passive"))
    )
    (net (code "72") (name "OUT7.1") (class "Default")
      (node (ref "CON1") (pin "2") (pinfunction "2_2") (pintype "bidirectional"))
      (node (ref "T1") (pin "6") (pinfunction "D_6") (pintype "passive"))
    )
    (net (code "73") (name "OUT7.2") (class "Default")
      (node (ref "CON1") (pin "3") (pinfunction "3_3") (pintype "bidirectional"))
      (node (ref "T1") (pin "8") (pinfunction "D_8") (pintype "passive"))
    )
    (net (code "74") (name "T_BLANK") (class "Default")
      (node (ref "IC1") (pin "2") (pinfunction "BLANK_2") (pintype "bidirectional"))
      (node (ref "IC2") (pin "32") (pinfunction "RC0/TIOSO/T13CKI_32") (pintype "bidirectional"))
      (node (ref "PIGGY_SIG") (pin "8") (pinfunction "8_8") (pintype "passive"))
    )
    (net (code "75") (name "T_BOOT") (class "Default")
      (node (ref "BOOT") (pin "1") (pinfunction "1_1") (pintype "passive"))
      (node (ref "IC2") (pin "20") (pinfunction "RA1/AN1_20") (pintype "bidirectional"))
      (node (ref "R31") (pin "1") (pinfunction "1_1") (pintype "passive"))
    )
    (net (code "76") (name "T_LATCH") (class "Default")
      (node (ref "IC1") (pin "30") (pinfunction "LATCH_30") (pintype "bidirectional"))
      (node (ref "IC2") (pin "11") (pinfunction "RB3/AN9/CCP2/VPO_11") (pintype "bidirectional"))
      (node (ref "PIGGY_SIG") (pin "6") (pinfunction "6_6") (pintype "passive"))
    )
    (net (code "77") (name "T_MISO") (class "Default")
      (node (ref "IC2") (pin "8") (pinfunction "RB0/AN12/INT0/LFT0/SDI/SDA_8") (pintype "bidirectional"))
      (node (ref "PIGGY_SIG") (pin "1") (pinfunction "1_1") (pintype "passive"))
    )
    (net (code "78") (name "T_MISO_LOOP") (class "Default")
      (node (ref "IC1") (pin "29") (pinfunction "SOUT_29") (pintype "bidirectional"))
      (node (ref "PIGGY_SIG") (pin "2") (pinfunction "2_2") (pintype "passive"))
    )
    (net (code "79") (name "T_MOSI") (class "Default")
      (node (ref "IC1") (pin "4") (pinfunction "SIN_4") (pintype "bidirectional"))
      (node (ref "IC2") (pin "1") (pinfunction "RC7/RX/DT/SDO_1") (pintype "bidirectional"))
    )
    (net (code "80") (name "T_POWER") (class "Default")
      (node (ref "IC2") (pin "15") (pinfunction "RB5/KBI1/PGM_15") (pintype "bidirectional"))
      (node (ref "PIGGY_SIG") (pin "5") (pinfunction "5_5") (pintype "passive"))
      (node (ref "R28") (pin "1") (pinfunction "1_1") (pintype "passive"))
      (node (ref "T13") (pin "2") (pinfunction "N-G_2") (pintype "passive"))
      (node (ref "T13") (pin "4") (pinfunction "P-G_4") (pintype "passive"))
    )
    (net (code "81") (name "T_SCK") (class "Default")
      (node (ref "IC1") (pin "3") (pinfunction "SCK_3") (pintype "bidirectional"))
      (node (ref "IC2") (pin "9") (pinfunction "RB1/AN10/INT1/SCK/SCL_9") (pintype "bidirectional"))
      (node (ref "PIGGY_SIG") (pin "3") (pinfunction "3_3") (pintype "passive"))
    )
    (net (code "82") (name "USB_D+") (class "Default")
      (node (ref "IC2") (pin "43") (pinfunction "RC5/D+/VP_43") (pintype "bidirectional"))
      (node (ref "PLUG_USB") (pin "D+") (pinfunction "D+_D+") (pintype "bidirectional"))
    )
    (net (code "83") (name "USB_D-") (class "Default")
      (node (ref "IC2") (pin "42") (pinfunction "RC4/D-/VM_42") (pintype "bidirectional"))
      (node (ref "PLUG_USB") (pin "D-") (pinfunction "D-_D-") (pintype "bidirectional"))
    )
    (net (code "84") (name "USB_SENSE") (class "Default")
      (node (ref "PLUG_USB") (pin "VUSB") (pinfunction "VBUS_VUSB") (pintype "bidirectional"))
      (node (ref "R26") (pin "1") (pinfunction "1_1") (pintype "passive"))
    )
    (net (code "85") (name "unconnected-(BOOT-Pad2)") (class "Default")
      (node (ref "BOOT") (pin "2") (pinfunction "2_2") (pintype "passive"))
    )
    (net (code "86") (name "unconnected-(BOOT-Pad4)") (class "Default")
      (node (ref "BOOT") (pin "4") (pinfunction "4_4") (pintype "passive"))
    )
    (net (code "87") (name "unconnected-(IC2-NC{slash}ICPORTS-Pad34)") (class "Default")
      (node (ref "IC2") (pin "34") (pinfunction "NC/ICPORTS_34") (pintype "input"))
    )
    (net (code "88") (name "unconnected-(IC2-RA2{slash}AN2{slash}VREF-{slash}CVREF-Pad21)") (class "Default")
      (node (ref "IC2") (pin "21") (pinfunction "RA2/AN2/VREF-/CVREF_21") (pintype "bidirectional"))
    )
    (net (code "89") (name "unconnected-(IC2-RA3{slash}AN3{slash}VREF+-Pad22)") (class "Default")
      (node (ref "IC2") (pin "22") (pinfunction "RA3/AN3/VREF+_22") (pintype "bidirectional"))
    )
    (net (code "90") (name "unconnected-(IC2-RA4{slash}T0CKI{slash}CIOUT{slash}RCV-Pad23)") (class "Default")
      (node (ref "IC2") (pin "23") (pinfunction "RA4/T0CKI/CIOUT/RCV_23") (pintype "bidirectional"))
    )
    (net (code "91") (name "unconnected-(IC2-RA5{slash}AN4{slash}~{SS}{slash}HLVDIN{slash}C2OUT-Pad24)") (class "Default")
      (node (ref "IC2") (pin "24") (pinfunction "RA5/AN4/~{SS}/HLVDIN/C2OUT_24") (pintype "bidirectional"))
    )
    (net (code "92") (name "unconnected-(IC2-RB6{slash}KBI2{slash}PGC-Pad16)") (class "Default")
      (node (ref "IC2") (pin "16") (pinfunction "RB6/KBI2/PGC_16") (pintype "bidirectional"))
    )
    (net (code "93") (name "unconnected-(IC2-RB7{slash}BKI3{slash}PGD-Pad17)") (class "Default")
      (node (ref "IC2") (pin "17") (pinfunction "RB7/BKI3/PGD_17") (pintype "bidirectional"))
    )
    (net (code "94") (name "unconnected-(IC2-RD0{slash}SPP0-Pad38)") (class "Default")
      (node (ref "IC2") (pin "38") (pinfunction "RD0/SPP0_38") (pintype "bidirectional"))
    )
    (net (code "95") (name "unconnected-(IC2-RD1{slash}SPP1-Pad39)") (class "Default")
      (node (ref "IC2") (pin "39") (pinfunction "RD1/SPP1_39") (pintype "bidirectional"))
    )
    (net (code "96") (name "unconnected-(IC2-RD2{slash}SPP2-Pad40)") (class "Default")
      (node (ref "IC2") (pin "40") (pinfunction "RD2/SPP2_40") (pintype "bidirectional"))
    )
    (net (code "97") (name "unconnected-(IC2-RD3{slash}SPP3-Pad41)") (class "Default")
      (node (ref "IC2") (pin "41") (pinfunction "RD3/SPP3_41") (pintype "bidirectional"))
    )
    (net (code "98") (name "unconnected-(IC2-RD4{slash}SPP4-Pad2)") (class "Default")
      (node (ref "IC2") (pin "2") (pinfunction "RD4/SPP4_2") (pintype "bidirectional"))
    )
    (net (code "99") (name "unconnected-(IC2-RD5{slash}SPP5{slash}P1B-Pad3)") (class "Default")
      (node (ref "IC2") (pin "3") (pinfunction "RD5/SPP5/P1B_3") (pintype "bidirectional"))
    )
    (net (code "100") (name "unconnected-(IC2-RD6{slash}SPP6{slash}P1C-Pad4)") (class "Default")
      (node (ref "IC2") (pin "4") (pinfunction "RD6/SPP6/P1C_4") (pintype "bidirectional"))
    )
    (net (code "101") (name "unconnected-(IC2-RD7{slash}SPP7{slash}P1D-Pad5)") (class "Default")
      (node (ref "IC2") (pin "5") (pinfunction "RD7/SPP7/P1D_5") (pintype "bidirectional"))
    )
    (net (code "102") (name "unconnected-(IC2-RE0{slash}AN5{slash}CK1SPP-Pad25)") (class "Default")
      (node (ref "IC2") (pin "25") (pinfunction "RE0/AN5/CK1SPP_25") (pintype "bidirectional"))
    )
    (net (code "103") (name "unconnected-(IC2-RE1{slash}AN6{slash}CK2SPP-Pad26)") (class "Default")
      (node (ref "IC2") (pin "26") (pinfunction "RE1/AN6/CK2SPP_26") (pintype "bidirectional"))
    )
    (net (code "104") (name "unconnected-(IC2-RE2{slash}AN7{slash}OESPP-Pad27)") (class "Default")
      (node (ref "IC2") (pin "27") (pinfunction "RE2/AN7/OESPP_27") (pintype "bidirectional"))
    )
    (net (code "105") (name "unconnected-(IC2-~{MCLR}{slash}VPP{slash}RE3-Pad18)") (class "Default")
      (node (ref "IC2") (pin "18") (pinfunction "~{MCLR}/VPP/RE3_18") (pintype "input"))
    )
    (net (code "106") (name "unconnected-(IC3-EN-Pad3)") (class "Default")
      (node (ref "IC3") (pin "3") (pinfunction "EN_3") (pintype "bidirectional"))
    )
    (net (code "107") (name "unconnected-(ICSP-Pad6)") (class "Default")
      (node (ref "ICSP") (pin "6") (pinfunction "6_6") (pintype "passive"))
    )
    (net (code "108") (name "unconnected-(IR-Pad2)") (class "Default")
      (node (ref "IR") (pin "2") (pinfunction "2_2") (pintype "passive"))
    )
    (net (code "109") (name "unconnected-(PLUG_LDR-Pad3)") (class "Default")
      (node (ref "PLUG_LDR") (pin "3") (pinfunction "3_3") (pintype "passive"))
    )
    (net (code "110") (name "unconnected-(PLUG_LDR-Pad4)") (class "Default")
      (node (ref "PLUG_LDR") (pin "4") (pinfunction "4_4") (pintype "passive"))
    )
    (net (code "111") (name "unconnected-(T13-D-Pad6)") (class "Default")
      (node (ref "T13") (pin "6") (pinfunction "D_6") (pintype "passive"))
    )
    (net (code "112") (name "unconnected-(T13-D-Pad7)") (class "Default")
      (node (ref "T13") (pin "7") (pinfunction "D_7") (pintype "passive"))
    )
    (net (code "113") (name "unconnected-(T13-D-Pad8)") (class "Default")
      (node (ref "T13") (pin "8") (pinfunction "D_8") (pintype "passive"))
    )
  )
)
